# PMM.net
KiCad netlist of a schematic drawn in EAGLE
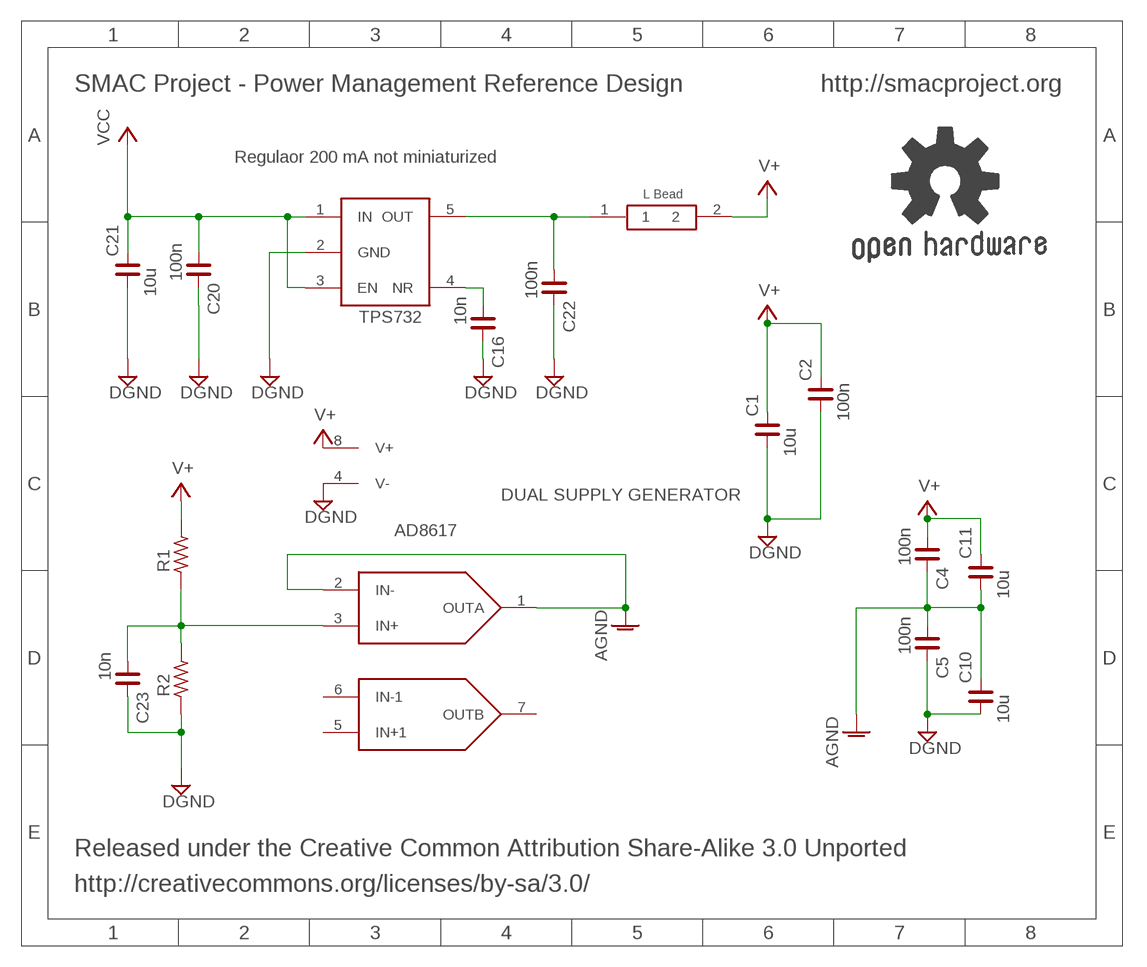
[diagram p0: schematic, sheet 1]

(export (version "E")
  (design (tool "Eeschema 10.0.6"))
  (components
    (comp (ref "C1")
      (value "10u")
      (footprint "eagle-import:C0402")
      (libsource (lib "eagle-import") (part "C_0402"))
    )
    (comp (ref "C2")
      (value "100n")
      (footprint "eagle-import:C0402")
      (libsource (lib "eagle-import") (part "C_0402"))
    )
    (comp (ref "C4")
      (value "100n")
      (footprint "eagle-import:C0402")
      (libsource (lib "eagle-import") (part "C_0402"))
    )
    (comp (ref "C5")
      (value "100n")
      (footprint "eagle-import:C0402")
      (libsource (lib "eagle-import") (part "C_0402"))
    )
    (comp (ref "C10")
      (value "10u")
      (footprint "eagle-import:C0402")
      (libsource (lib "eagle-import") (part "C_0402"))
    )
    (comp (ref "C11")
      (value "10u")
      (footprint "eagle-import:C0402")
      (libsource (lib "eagle-import") (part "C_0402"))
    )
    (comp (ref "C16")
      (value "10n")
      (footprint "eagle-import:C0402")
      (libsource (lib "eagle-import") (part "C_0402"))
    )
    (comp (ref "C20")
      (value "100n")
      (footprint "eagle-import:C0402")
      (libsource (lib "eagle-import") (part "C_0402"))
    )
    (comp (ref "C21")
      (value "10u")
      (footprint "eagle-import:C0402")
      (libsource (lib "eagle-import") (part "C_0402"))
    )
    (comp (ref "C22")
      (value "100n")
      (footprint "eagle-import:C0402")
      (libsource (lib "eagle-import") (part "C_0402"))
    )
    (comp (ref "C23")
      (value "10n")
      (footprint "eagle-import:C0402")
      (libsource (lib "eagle-import") (part "C_0402"))
    )
    (comp (ref "GOLD_ORB_SM1")
      (value "OSHWLOGO_REF_SM")
      (footprint "eagle-import:OSHW2REF")
      (libsource (lib "eagle-import") (part "OSHWLOGO_REF_SM"))
    )
    (comp (ref "IC1")
      (value "TPS732XX")
      (footprint "eagle-import:SOT23")
      (libsource (lib "eagle-import") (part "TPS732XX"))
    )
    (comp (ref "IC2")
      (value "AD8617")
      (footprint "eagle-import:MSOP8")
      (libsource (lib "eagle-import") (part "AD8617"))
    )
    (comp (ref "L-BEAD")
      (value "L-BEAD")
      (footprint "eagle-import:0402")
      (libsource (lib "eagle-import") (part "L-BEAD"))
    )
    (comp (ref "R1")
      (value "R_0402")
      (footprint "eagle-import:R0402")
      (libsource (lib "eagle-import") (part "R_0402"))
    )
    (comp (ref "R2")
      (value "R_0402")
      (footprint "eagle-import:R0402")
      (libsource (lib "eagle-import") (part "R_0402"))
    )
  )
  (nets
    (net (code "1") (name "AGND") (class "Default")
      (node (ref "C10") (pin "2") (pinfunction "2_2") (pintype "passive"))
      (node (ref "C11") (pin "1") (pinfunction "1_1") (pintype "passive"))
      (node (ref "C4") (pin "2") (pinfunction "2_2") (pintype "passive"))
      (node (ref "C5") (pin "1") (pinfunction "1_1") (pintype "passive"))
      (node (ref "IC2") (pin "1") (pinfunction "OUTA_1") (pintype "bidirectional"))
      (node (ref "IC2") (pin "2") (pinfunction "IN-_2") (pintype "bidirectional"))
    )
    (net (code "2") (name "DGND") (class "Default")
      (node (ref "C1") (pin "1") (pinfunction "1_1") (pintype "passive"))
      (node (ref "C10") (pin "1") (pinfunction "1_1") (pintype "passive"))
      (node (ref "C16") (pin "2") (pinfunction "2_2") (pintype "passive"))
      (node (ref "C2") (pin "1") (pinfunction "1_1") (pintype "passive"))
      (node (ref "C20") (pin "2") (pinfunction "2_2") (pintype "passive"))
      (node (ref "C21") (pin "1") (pinfunction "1_1") (pintype "passive"))
      (node (ref "C22") (pin "2") (pinfunction "2_2") (pintype "passive"))
      (node (ref "C23") (pin "2") (pinfunction "2_2") (pintype "passive"))
      (node (ref "C5") (pin "2") (pinfunction "2_2") (pintype "passive"))
      (node (ref "IC1") (pin "2") (pinfunction "GND_2") (pintype "bidirectional"))
      (node (ref "IC2") (pin "4") (pinfunction "V-_4") (pintype "bidirectional"))
      (node (ref "R2") (pin "1") (pinfunction "1_1") (pintype "passive"))
    )
    (net (code "3") (name "Net-(IC1-NR)") (class "Default")
      (node (ref "C16") (pin "1") (pinfunction "1_1") (pintype "passive"))
      (node (ref "IC1") (pin "4") (pinfunction "NR_4") (pintype "bidirectional"))
    )
    (net (code "4") (name "Net-(IC1-OUT)") (class "Default")
      (node (ref "C22") (pin "1") (pinfunction "1_1") (pintype "passive"))
      (node (ref "IC1") (pin "5") (pinfunction "OUT_5") (pintype "bidirectional"))
      (node (ref "L-BEAD") (pin "1") (pinfunction "1_1") (pintype "bidirectional"))
    )
    (net (code "5") (name "Net-(IC2-IN+)") (class "Default")
      (node (ref "C23") (pin "1") (pinfunction "1_1") (pintype "passive"))
      (node (ref "IC2") (pin "3") (pinfunction "IN+_3") (pintype "bidirectional"))
      (node (ref "R1") (pin "1") (pinfunction "1_1") (pintype "passive"))
      (node (ref "R2") (pin "2") (pinfunction "2_2") (pintype "passive"))
    )
    (net (code "6") (name "V+") (class "Default")
      (node (ref "C1") (pin "2") (pinfunction "2_2") (pintype "passive"))
      (node (ref "C11") (pin "2") (pinfunction "2_2") (pintype "passive"))
      (node (ref "C2") (pin "2") (pinfunction "2_2") (pintype "passive"))
      (node (ref "C4") (pin "1") (pinfunction "1_1") (pintype "passive"))
      (node (ref "IC2") (pin "8") (pinfunction "V+_8") (pintype "bidirectional"))
      (node (ref "L-BEAD") (pin "2") (pinfunction "2_2") (pintype "bidirectional"))
      (node (ref "R1") (pin "2") (pinfunction "2_2") (pintype "passive"))
    )
    (net (code "7") (name "VCC") (class "Default")
      (node (ref "C20") (pin "1") (pinfunction "1_1") (pintype "passive"))
      (node (ref "C21") (pin "2") (pinfunction "2_2") (pintype "passive"))
      (node (ref "IC1") (pin "1") (pinfunction "IN_1") (pintype "bidirectional"))
      (node (ref "IC1") (pin "3") (pinfunction "EN_3") (pintype "bidirectional"))
    )
    (net (code "8") (name "unconnected-(IC2-IN+1-Pad5)") (class "Default")
      (node (ref "IC2") (pin "5") (pinfunction "IN+1_5") (pintype "bidirectional"))
    )
    (net (code "9") (name "unconnected-(IC2-IN-1-Pad6)") (class "Default")
      (node (ref "IC2") (pin "6") (pinfunction "IN-1_6") (pintype "bidirectional"))
    )
    (net (code "10") (name "unconnected-(IC2-OUTB-Pad7)") (class "Default")
      (node (ref "IC2") (pin "7") (pinfunction "OUTB_7") (pintype "bidirectional"))
    )
  )
)
